# FPGA_CFG.net
KiCad netlist of a schematic drawn in Altium Designer
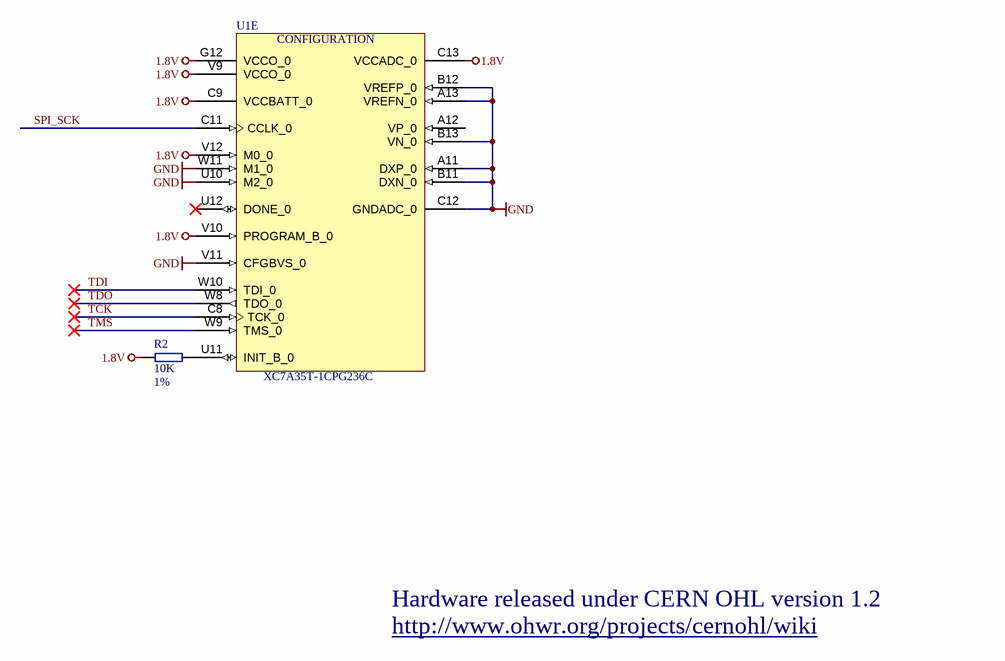
[diagram p0: FPGA_CFG.SchDoc]

(export (version "E")
  (design (tool "Eeschema 10.0.6"))
  (components
    (comp (ref "R2")
      (value "10K")
      (footprint "RESC0603X26N")
      (description "WID SMD 10K 1% 0,05W")
      (fields (field (name "TOLERANCE") "1%"))
      (libsource (lib "TE") (part "RES"))
    )
    (comp (ref "U1")
      (value "XC7A35T-1CPG236C")
      (footprint "XC7AxxT-CPG236")
      (libsource (lib "TE") (part "XC7A35T-CPG236"))
    )
  )
  (nets
    (net (code "1") (name "/SPI_SCK") (class "Default")
      (node (ref "U1") (pin "C11") (pinfunction "CCLK_0_C11") (pintype "input"))
    )
    (net (code "2") (name "/TCK") (class "Default")
      (node (ref "U1") (pin "C8") (pinfunction "TCK_0_C8") (pintype "input+no_connect"))
    )
    (net (code "3") (name "/TDI") (class "Default")
      (node (ref "U1") (pin "W10") (pinfunction "TDI_0_W10") (pintype "input+no_connect"))
    )
    (net (code "4") (name "/TDO") (class "Default")
      (node (ref "U1") (pin "W8") (pinfunction "TDO_0_W8") (pintype "output+no_connect"))
    )
    (net (code "5") (name "/TMS") (class "Default")
      (node (ref "U1") (pin "W9") (pinfunction "TMS_0_W9") (pintype "input+no_connect"))
    )
    (net (code "6") (name "1.8V") (class "Default")
      (node (ref "R2") (pin "1") (pinfunction "1_1") (pintype "passive"))
      (node (ref "U1") (pin "C13") (pinfunction "VCCADC_0_C13") (pintype "power_in"))
      (node (ref "U1") (pin "C9") (pinfunction "VCCBATT_0_C9") (pintype "power_in"))
      (node (ref "U1") (pin "G12") (pinfunction "VCCO_0_G12") (pintype "power_in"))
      (node (ref "U1") (pin "V10") (pinfunction "PROGRAM_B_0_V10") (pintype "input"))
      (node (ref "U1") (pin "V12") (pinfunction "M0_0_V12") (pintype "input"))
      (node (ref "U1") (pin "V9") (pinfunction "VCCO_0_V9") (pintype "power_in"))
    )
    (net (code "7") (name "GND") (class "Default")
      (node (ref "U1") (pin "A11") (pinfunction "DXP_0_A11") (pintype "input"))
      (node (ref "U1") (pin "A13") (pinfunction "VREFN_0_A13") (pintype "input"))
      (node (ref "U1") (pin "B11") (pinfunction "DXN_0_B11") (pintype "input"))
      (node (ref "U1") (pin "B12") (pinfunction "VREFP_0_B12") (pintype "input"))
      (node (ref "U1") (pin "B13") (pinfunction "VN_0_B13") (pintype "input"))
      (node (ref "U1") (pin "C12") (pinfunction "GNDADC_0_C12") (pintype "power_in"))
      (node (ref "U1") (pin "U10") (pinfunction "M2_0_U10") (pintype "input"))
      (node (ref "U1") (pin "V11") (pinfunction "CFGBVS_0_V11") (pintype "input"))
      (node (ref "U1") (pin "W11") (pinfunction "M1_0_W11") (pintype "input"))
    )
    (net (code "8") (name "Net-(U1E-INIT_B_0)") (class "Default")
      (node (ref "R2") (pin "2") (pinfunction "2_2") (pintype "passive"))
      (node (ref "U1") (pin "U11") (pinfunction "INIT_B_0_U11") (pintype "bidirectional"))
    )
    (net (code "9") (name "unconnected-(U1E-DONE_0-PadU12)") (class "Default")
      (node (ref "U1") (pin "U12") (pinfunction "DONE_0_U12") (pintype "bidirectional+no_connect"))
    )
    (net (code "10") (name "unconnected-(U1E-VP_0-PadA12)") (class "Default")
      (node (ref "U1") (pin "A12") (pinfunction "VP_0_A12") (pintype "input"))
    )
  )
)
